# TrackBalloptics.net
KiCad netlist of a schematic drawn in Altium Designer
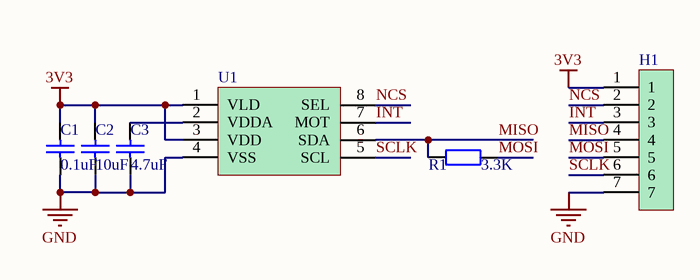
[diagram p0: TrackBalloptics.SchDoc]

(export (version "E")
  (design (tool "Eeschema 10.0.6"))
  (components
    (comp (ref "C1")
      (value "0.1uF")
      (footprint "0603")
      (description "贴片电容 0603")
      (libsource (lib "MT_Device") (part "CAP_0603"))
    )
    (comp (ref "C2")
      (value "10uF")
      (footprint "0603")
      (description "贴片电容 0603")
      (libsource (lib "MT_Device") (part "CAP_0603"))
    )
    (comp (ref "C3")
      (value "4.7uF")
      (footprint "0603")
      (description "贴片电容 0603")
      (libsource (lib "MT_Device") (part "CAP_0603"))
    )
    (comp (ref "H1")
      (value "SH1.25mm_7P")
      (footprint "SH1.25MM_7P")
      (libsource (lib "MT_Connector") (part "SH1.25mm_7P"))
    )
    (comp (ref "R1")
      (value "3.3K")
      (footprint "R_0603")
      (description "电阻 0603")
      (libsource (lib "MT_Device") (part "RES_0603"))
    )
    (comp (ref "U1")
      (value "Optical Tracking Miniature Chip")
      (footprint "PAT9125EL")
      (libsource (lib "MT_Chip") (part "PAT9125EL"))
    )
  )
  (nets
    (net (code "1") (name "/INT") (class "Default")
      (node (ref "H1") (pin "3") (pinfunction "3_3") (pintype "passive"))
      (node (ref "U1") (pin "7") (pinfunction "MOT_7") (pintype "passive"))
    )
    (net (code "2") (name "/MISO") (class "Default")
      (node (ref "H1") (pin "4") (pinfunction "4_4") (pintype "passive"))
      (node (ref "R1") (pin "1") (pinfunction "1_1") (pintype "passive"))
      (node (ref "U1") (pin "6") (pinfunction "SDA_6") (pintype "passive"))
    )
    (net (code "3") (name "/MOSI") (class "Default")
      (node (ref "H1") (pin "5") (pinfunction "5_5") (pintype "passive"))
      (node (ref "R1") (pin "2") (pinfunction "2_2") (pintype "passive"))
    )
    (net (code "4") (name "/NCS") (class "Default")
      (node (ref "H1") (pin "2") (pinfunction "2_2") (pintype "passive"))
      (node (ref "U1") (pin "8") (pinfunction "SEL_8") (pintype "passive"))
    )
    (net (code "5") (name "/SCLK") (class "Default")
      (node (ref "H1") (pin "6") (pinfunction "6_6") (pintype "passive"))
      (node (ref "U1") (pin "5") (pinfunction "SCL_5") (pintype "passive"))
    )
    (net (code "6") (name "3V3") (class "Default")
      (node (ref "C1") (pin "2") (pinfunction "2_2") (pintype "passive"))
      (node (ref "C2") (pin "2") (pinfunction "2_2") (pintype "passive"))
      (node (ref "H1") (pin "1") (pinfunction "1_1") (pintype "passive"))
      (node (ref "U1") (pin "1") (pinfunction "VLD_1") (pintype "passive"))
      (node (ref "U1") (pin "3") (pinfunction "VDD_3") (pintype "passive"))
    )
    (net (code "7") (name "GND") (class "Default")
      (node (ref "C1") (pin "1") (pinfunction "1_1") (pintype "passive"))
      (node (ref "C2") (pin "1") (pinfunction "1_1") (pintype "passive"))
      (node (ref "C3") (pin "1") (pinfunction "1_1") (pintype "passive"))
      (node (ref "H1") (pin "7") (pinfunction "7_7") (pintype "passive"))
      (node (ref "U1") (pin "4") (pinfunction "VSS_4") (pintype "passive"))
    )
    (net (code "8") (name "Net-(U1-VDDA)") (class "Default")
      (node (ref "C3") (pin "2") (pinfunction "2_2") (pintype "passive"))
      (node (ref "U1") (pin "2") (pinfunction "VDDA_2") (pintype "passive"))
    )
  )
)
